# drv8305_instaspin_driver_adapter.net
KiCad netlist of a schematic drawn in Altium Designer
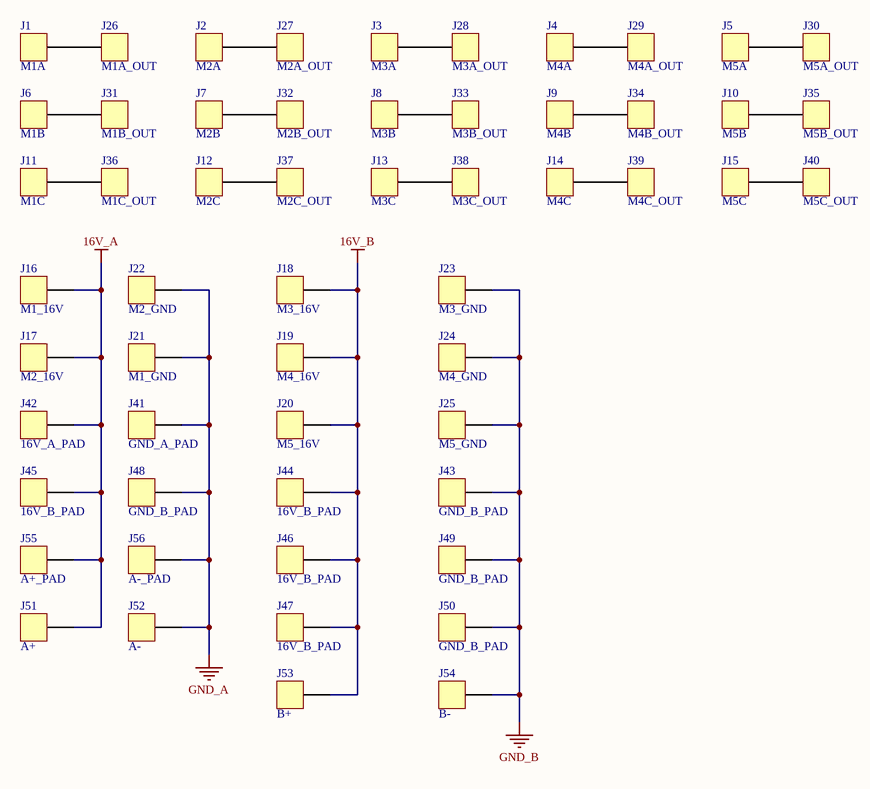
[diagram p0: drv8305_instaspin_driver_adapter.SchDoc]

(export (version "E")
  (design (tool "Eeschema 10.0.6"))
  (components
    (comp (ref "J1")
      (value "M1A")
      (footprint "2MM-BULLET-PLUG-VIA")
      (libsource (lib "connectors") (part "HEADER-1"))
    )
    (comp (ref "J2")
      (value "M2A")
      (footprint "2MM-BULLET-PLUG-VIA")
      (libsource (lib "connectors") (part "HEADER-1"))
    )
    (comp (ref "J3")
      (value "M3A")
      (footprint "2MM-BULLET-PLUG-VIA")
      (libsource (lib "connectors") (part "HEADER-1"))
    )
    (comp (ref "J4")
      (value "M4A")
      (footprint "2MM-BULLET-PLUG-VIA")
      (libsource (lib "connectors") (part "HEADER-1"))
    )
    (comp (ref "J5")
      (value "M5A")
      (footprint "2MM-BULLET-PLUG-VIA")
      (libsource (lib "connectors") (part "HEADER-1"))
    )
    (comp (ref "J6")
      (value "M1B")
      (footprint "2MM-BULLET-PLUG-VIA")
      (libsource (lib "connectors") (part "HEADER-1"))
    )
    (comp (ref "J7")
      (value "M2B")
      (footprint "2MM-BULLET-PLUG-VIA")
      (libsource (lib "connectors") (part "HEADER-1"))
    )
    (comp (ref "J8")
      (value "M3B")
      (footprint "2MM-BULLET-PLUG-VIA")
      (libsource (lib "connectors") (part "HEADER-1"))
    )
    (comp (ref "J9")
      (value "M4B")
      (footprint "2MM-BULLET-PLUG-VIA")
      (libsource (lib "connectors") (part "HEADER-1"))
    )
    (comp (ref "J10")
      (value "M5B")
      (footprint "2MM-BULLET-PLUG-VIA")
      (libsource (lib "connectors") (part "HEADER-1"))
    )
    (comp (ref "J11")
      (value "M1C")
      (footprint "2MM-BULLET-PLUG-VIA")
      (libsource (lib "connectors") (part "HEADER-1"))
    )
    (comp (ref "J12")
      (value "M2C")
      (footprint "2MM-BULLET-PLUG-VIA")
      (libsource (lib "connectors") (part "HEADER-1"))
    )
    (comp (ref "J13")
      (value "M3C")
      (footprint "2MM-BULLET-PLUG-VIA")
      (libsource (lib "connectors") (part "HEADER-1"))
    )
    (comp (ref "J14")
      (value "M4C")
      (footprint "2MM-BULLET-PLUG-VIA")
      (libsource (lib "connectors") (part "HEADER-1"))
    )
    (comp (ref "J15")
      (value "M5C")
      (footprint "2MM-BULLET-PLUG-VIA")
      (libsource (lib "connectors") (part "HEADER-1"))
    )
    (comp (ref "J16")
      (value "M1_16V")
      (footprint "2MM-BULLET-PLUG-VIA")
      (libsource (lib "connectors") (part "HEADER-1"))
    )
    (comp (ref "J17")
      (value "M2_16V")
      (footprint "2MM-BULLET-PLUG-VIA")
      (libsource (lib "connectors") (part "HEADER-1"))
    )
    (comp (ref "J18")
      (value "M3_16V")
      (footprint "2MM-BULLET-PLUG-VIA")
      (libsource (lib "connectors") (part "HEADER-1"))
    )
    (comp (ref "J19")
      (value "M4_16V")
      (footprint "2MM-BULLET-PLUG-VIA")
      (libsource (lib "connectors") (part "HEADER-1"))
    )
    (comp (ref "J20")
      (value "M5_16V")
      (footprint "2MM-BULLET-PLUG-VIA")
      (libsource (lib "connectors") (part "HEADER-1"))
    )
    (comp (ref "J21")
      (value "M1_GND")
      (footprint "2MM-BULLET-PLUG-VIA")
      (libsource (lib "connectors") (part "HEADER-1"))
    )
    (comp (ref "J22")
      (value "M2_GND")
      (footprint "2MM-BULLET-PLUG-VIA")
      (libsource (lib "connectors") (part "HEADER-1"))
    )
    (comp (ref "J23")
      (value "M3_GND")
      (footprint "2MM-BULLET-PLUG-VIA")
      (libsource (lib "connectors") (part "HEADER-1"))
    )
    (comp (ref "J24")
      (value "M4_GND")
      (footprint "2MM-BULLET-PLUG-VIA")
      (libsource (lib "connectors") (part "HEADER-1"))
    )
    (comp (ref "J25")
      (value "M5_GND")
      (footprint "2MM-BULLET-PLUG-VIA")
      (libsource (lib "connectors") (part "HEADER-1"))
    )
    (comp (ref "J26") (value "M1A_OUT") (footprint "POWER-PAD") (libsource (lib "") (part "HEADER-1_1")))
    (comp (ref "J27") (value "M2A_OUT") (footprint "POWER-PAD") (libsource (lib "") (part "HEADER-1_1")))
    (comp (ref "J28") (value "M3A_OUT") (footprint "POWER-PAD") (libsource (lib "") (part "HEADER-1_1")))
    (comp (ref "J29") (value "M4A_OUT") (footprint "POWER-PAD") (libsource (lib "") (part "HEADER-1_1")))
    (comp (ref "J30") (value "M5A_OUT") (footprint "POWER-PAD") (libsource (lib "") (part "HEADER-1_1")))
    (comp (ref "J31") (value "M1B_OUT") (footprint "POWER-PAD") (libsource (lib "") (part "HEADER-1_1")))
    (comp (ref "J32") (value "M2B_OUT") (footprint "POWER-PAD") (libsource (lib "") (part "HEADER-1_1")))
    (comp (ref "J33") (value "M3B_OUT") (footprint "POWER-PAD") (libsource (lib "") (part "HEADER-1_1")))
    (comp (ref "J34") (value "M4B_OUT") (footprint "POWER-PAD") (libsource (lib "") (part "HEADER-1_1")))
    (comp (ref "J35") (value "M5B_OUT") (footprint "POWER-PAD") (libsource (lib "") (part "HEADER-1_1")))
    (comp (ref "J36") (value "M1C_OUT") (footprint "POWER-PAD") (libsource (lib "") (part "HEADER-1_1")))
    (comp (ref "J37") (value "M2C_OUT") (footprint "POWER-PAD") (libsource (lib "") (part "HEADER-1_1")))
    (comp (ref "J38") (value "M3C_OUT") (footprint "POWER-PAD") (libsource (lib "") (part "HEADER-1_1")))
    (comp (ref "J39") (value "M4C_OUT") (footprint "POWER-PAD") (libsource (lib "") (part "HEADER-1_1")))
    (comp (ref "J40") (value "M5C_OUT") (footprint "POWER-PAD") (libsource (lib "") (part "HEADER-1_1")))
    (comp (ref "J41")
      (value "GND_A_PAD")
      (footprint "POWER-PAD")
      (libsource (lib "connectors") (part "HEADER-1"))
    )
    (comp (ref "J42")
      (value "16V_A_PAD")
      (footprint "POWER-PAD")
      (libsource (lib "connectors") (part "HEADER-1"))
    )
    (comp (ref "J43")
      (value "GND_B_PAD")
      (footprint "POWER-PAD")
      (libsource (lib "connectors") (part "HEADER-1"))
    )
    (comp (ref "J44")
      (value "16V_B_PAD")
      (footprint "POWER-PAD")
      (libsource (lib "connectors") (part "HEADER-1"))
    )
    (comp (ref "J45")
      (value "16V_B_PAD")
      (footprint "POWER-PAD")
      (libsource (lib "connectors") (part "HEADER-1"))
    )
    (comp (ref "J46")
      (value "16V_B_PAD")
      (footprint "POWER-PAD")
      (libsource (lib "connectors") (part "HEADER-1"))
    )
    (comp (ref "J47")
      (value "16V_B_PAD")
      (footprint "POWER-PAD")
      (libsource (lib "connectors") (part "HEADER-1"))
    )
    (comp (ref "J48")
      (value "GND_B_PAD")
      (footprint "POWER-PAD")
      (libsource (lib "connectors") (part "HEADER-1"))
    )
    (comp (ref "J49")
      (value "GND_B_PAD")
      (footprint "POWER-PAD")
      (libsource (lib "connectors") (part "HEADER-1"))
    )
    (comp (ref "J50")
      (value "GND_B_PAD")
      (footprint "POWER-PAD")
      (libsource (lib "connectors") (part "HEADER-1"))
    )
    (comp (ref "J51") (value "A+") (footprint "2MM-BANANA-VIA") (libsource (lib "") (part "HEADER-1_2")))
    (comp (ref "J52") (value "A-") (footprint "2MM-BANANA-VIA") (libsource (lib "") (part "HEADER-1_2")))
    (comp (ref "J53") (value "B+") (footprint "2MM-BANANA-VIA") (libsource (lib "") (part "HEADER-1_2")))
    (comp (ref "J54") (value "B-") (footprint "2MM-BANANA-VIA") (libsource (lib "") (part "HEADER-1_2")))
    (comp (ref "J55") (value "A+_PAD") (footprint "POWER-PAD") (libsource (lib "") (part "HEADER-1_2")))
    (comp (ref "J56") (value "A-_PAD") (footprint "POWER-PAD") (libsource (lib "") (part "HEADER-1_2")))
  )
  (nets
    (net (code "1") (name "16V_A") (class "Default")
      (node (ref "J16") (pin "1") (pinfunction "1_1") (pintype "passive"))
      (node (ref "J17") (pin "1") (pinfunction "1_1") (pintype "passive"))
      (node (ref "J42") (pin "1") (pinfunction "1_1") (pintype "passive"))
      (node (ref "J45") (pin "1") (pinfunction "1_1") (pintype "passive"))
      (node (ref "J51") (pin "1") (pinfunction "1_1") (pintype "passive"))
      (node (ref "J55") (pin "1") (pinfunction "1_1") (pintype "passive"))
    )
    (net (code "2") (name "16V_B") (class "Default")
      (node (ref "J18") (pin "1") (pinfunction "1_1") (pintype "passive"))
      (node (ref "J19") (pin "1") (pinfunction "1_1") (pintype "passive"))
      (node (ref "J20") (pin "1") (pinfunction "1_1") (pintype "passive"))
      (node (ref "J44") (pin "1") (pinfunction "1_1") (pintype "passive"))
      (node (ref "J46") (pin "1") (pinfunction "1_1") (pintype "passive"))
      (node (ref "J47") (pin "1") (pinfunction "1_1") (pintype "passive"))
      (node (ref "J53") (pin "1") (pinfunction "1_1") (pintype "passive"))
    )
    (net (code "3") (name "GND_A") (class "Default")
      (node (ref "J21") (pin "1") (pinfunction "1_1") (pintype "passive"))
      (node (ref "J22") (pin "1") (pinfunction "1_1") (pintype "passive"))
      (node (ref "J41") (pin "1") (pinfunction "1_1") (pintype "passive"))
      (node (ref "J48") (pin "1") (pinfunction "1_1") (pintype "passive"))
      (node (ref "J52") (pin "1") (pinfunction "1_1") (pintype "passive"))
      (node (ref "J56") (pin "1") (pinfunction "1_1") (pintype "passive"))
    )
    (net (code "4") (name "GND_B") (class "Default")
      (node (ref "J23") (pin "1") (pinfunction "1_1") (pintype "passive"))
      (node (ref "J24") (pin "1") (pinfunction "1_1") (pintype "passive"))
      (node (ref "J25") (pin "1") (pinfunction "1_1") (pintype "passive"))
      (node (ref "J43") (pin "1") (pinfunction "1_1") (pintype "passive"))
      (node (ref "J49") (pin "1") (pinfunction "1_1") (pintype "passive"))
      (node (ref "J50") (pin "1") (pinfunction "1_1") (pintype "passive"))
      (node (ref "J54") (pin "1") (pinfunction "1_1") (pintype "passive"))
    )
    (net (code "5") (name "Net-(J1-Pad1)") (class "Default")
      (node (ref "J1") (pin "1") (pinfunction "1_1") (pintype "passive"))
      (node (ref "J26") (pin "1") (pinfunction "1_1") (pintype "passive"))
    )
    (net (code "6") (name "Net-(J2-Pad1)") (class "Default")
      (node (ref "J2") (pin "1") (pinfunction "1_1") (pintype "passive"))
      (node (ref "J27") (pin "1") (pinfunction "1_1") (pintype "passive"))
    )
    (net (code "7") (name "Net-(J10-Pad1)") (class "Default")
      (node (ref "J10") (pin "1") (pinfunction "1_1") (pintype "passive"))
      (node (ref "J35") (pin "1") (pinfunction "1_1") (pintype "passive"))
    )
    (net (code "8") (name "Net-(J11-Pad1)") (class "Default")
      (node (ref "J11") (pin "1") (pinfunction "1_1") (pintype "passive"))
      (node (ref "J36") (pin "1") (pinfunction "1_1") (pintype "passive"))
    )
    (net (code "9") (name "Net-(J12-Pad1)") (class "Default")
      (node (ref "J12") (pin "1") (pinfunction "1_1") (pintype "passive"))
      (node (ref "J37") (pin "1") (pinfunction "1_1") (pintype "passive"))
    )
    (net (code "10") (name "Net-(J13-Pad1)") (class "Default")
      (node (ref "J13") (pin "1") (pinfunction "1_1") (pintype "passive"))
      (node (ref "J38") (pin "1") (pinfunction "1_1") (pintype "passive"))
    )
    (net (code "11") (name "Net-(J14-Pad1)") (class "Default")
      (node (ref "J14") (pin "1") (pinfunction "1_1") (pintype "passive"))
      (node (ref "J39") (pin "1") (pinfunction "1_1") (pintype "passive"))
    )
    (net (code "12") (name "Net-(J15-Pad1)") (class "Default")
      (node (ref "J15") (pin "1") (pinfunction "1_1") (pintype "passive"))
      (node (ref "J40") (pin "1") (pinfunction "1_1") (pintype "passive"))
    )
    (net (code "13") (name "Net-(J28-Pad1)") (class "Default")
      (node (ref "J28") (pin "1") (pinfunction "1_1") (pintype "passive"))
      (node (ref "J3") (pin "1") (pinfunction "1_1") (pintype "passive"))
    )
    (net (code "14") (name "Net-(J29-Pad1)") (class "Default")
      (node (ref "J29") (pin "1") (pinfunction "1_1") (pintype "passive"))
      (node (ref "J4") (pin "1") (pinfunction "1_1") (pintype "passive"))
    )
    (net (code "15") (name "Net-(J30-Pad1)") (class "Default")
      (node (ref "J30") (pin "1") (pinfunction "1_1") (pintype "passive"))
      (node (ref "J5") (pin "1") (pinfunction "1_1") (pintype "passive"))
    )
    (net (code "16") (name "Net-(J31-Pad1)") (class "Default")
      (node (ref "J31") (pin "1") (pinfunction "1_1") (pintype "passive"))
      (node (ref "J6") (pin "1") (pinfunction "1_1") (pintype "passive"))
    )
    (net (code "17") (name "Net-(J32-Pad1)") (class "Default")
      (node (ref "J32") (pin "1") (pinfunction "1_1") (pintype "passive"))
      (node (ref "J7") (pin "1") (pinfunction "1_1") (pintype "passive"))
    )
    (net (code "18") (name "Net-(J33-Pad1)") (class "Default")
      (node (ref "J33") (pin "1") (pinfunction "1_1") (pintype "passive"))
      (node (ref "J8") (pin "1") (pinfunction "1_1") (pintype "passive"))
    )
    (net (code "19") (name "Net-(J34-Pad1)") (class "Default")
      (node (ref "J34") (pin "1") (pinfunction "1_1") (pintype "passive"))
      (node (ref "J9") (pin "1") (pinfunction "1_1") (pintype "passive"))
    )
  )
)
